# dso_v3b.net
KiCad netlist of a schematic drawn in EAGLE
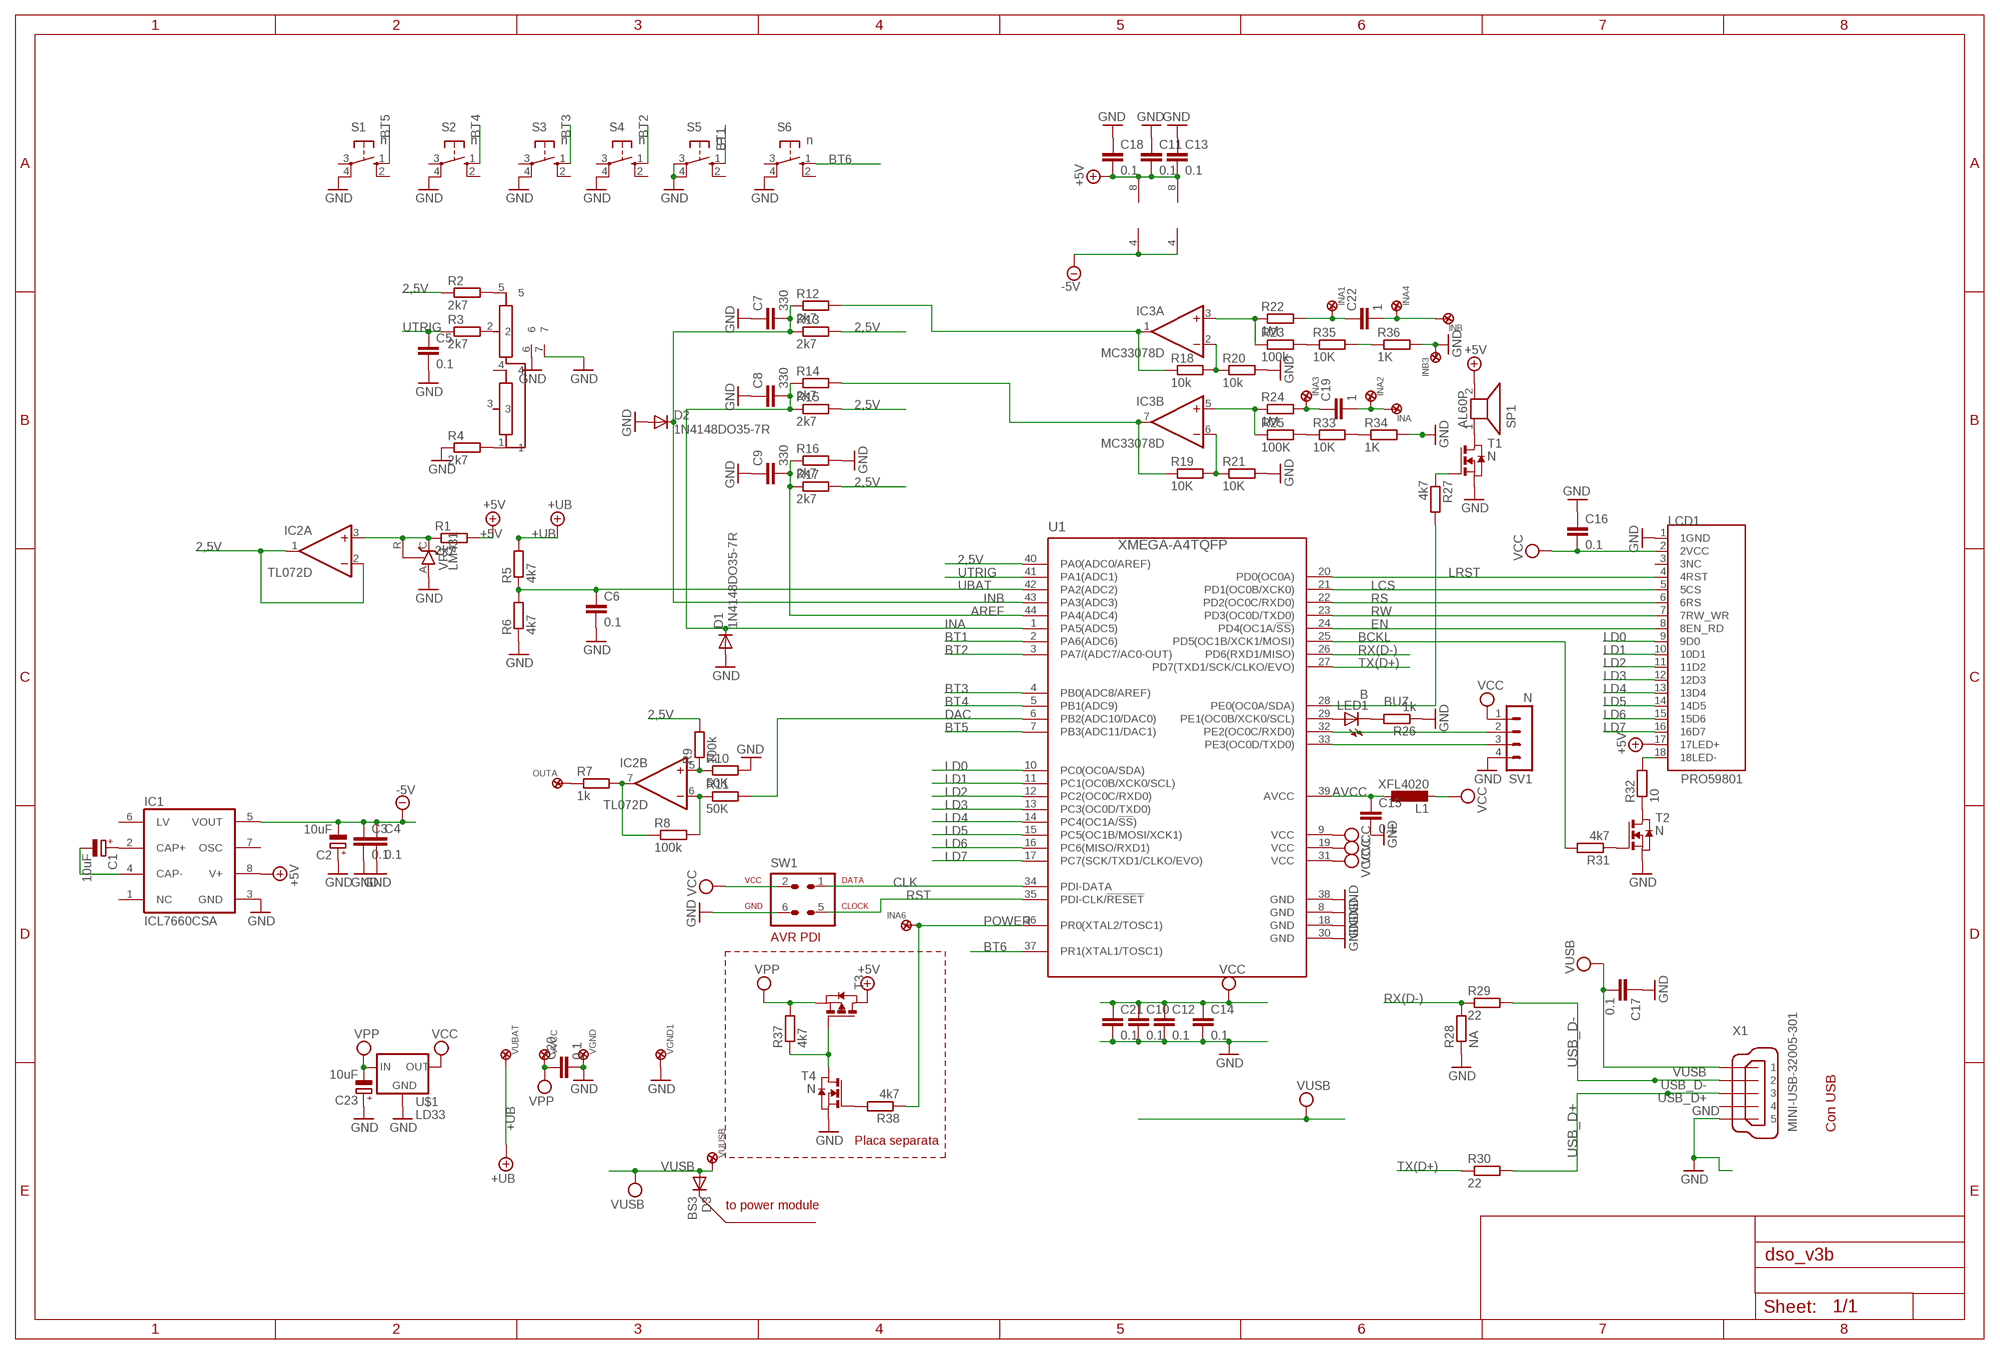
[diagram p0: schematic, sheet 1]

(export (version "E")
  (design (tool "Eeschema 10.0.6"))
  (components
    (comp (ref "C1")
      (value "10uF")
      (footprint "eagle-import:CT3528")
      (libsource (lib "eagle-import") (part "CPOL-EUCT3528"))
    )
    (comp (ref "C2")
      (value "10uF")
      (footprint "eagle-import:CT3528")
      (libsource (lib "eagle-import") (part "CPOL-EUCT3528"))
    )
    (comp (ref "C3")
      (value "0.1")
      (footprint "eagle-import:C0603")
      (libsource (lib "eagle-import") (part "C-EUC0603"))
    )
    (comp (ref "C4")
      (value "0.1")
      (footprint "eagle-import:C0603")
      (libsource (lib "eagle-import") (part "C-EUC0603"))
    )
    (comp (ref "C5")
      (value "0.1")
      (footprint "eagle-import:C0603")
      (libsource (lib "eagle-import") (part "C-EUC0603"))
    )
    (comp (ref "C6")
      (value "0.1")
      (footprint "eagle-import:C0603")
      (libsource (lib "eagle-import") (part "C-EUC0603"))
    )
    (comp (ref "C7")
      (value "330")
      (footprint "eagle-import:C025-024X044")
      (libsource (lib "eagle-import") (part "C-EU025-024X044"))
    )
    (comp (ref "C8")
      (value "330")
      (footprint "eagle-import:C025-024X044")
      (libsource (lib "eagle-import") (part "C-EU025-024X044"))
    )
    (comp (ref "C9")
      (value "330")
      (footprint "eagle-import:C025-024X044")
      (libsource (lib "eagle-import") (part "C-EU025-024X044"))
    )
    (comp (ref "C10")
      (value "0.1")
      (footprint "eagle-import:C0603")
      (libsource (lib "eagle-import") (part "C-EUC0603"))
    )
    (comp (ref "C11")
      (value "0.1")
      (footprint "eagle-import:C0603")
      (libsource (lib "eagle-import") (part "C-EUC0603"))
    )
    (comp (ref "C12")
      (value "0.1")
      (footprint "eagle-import:C0603")
      (libsource (lib "eagle-import") (part "C-EUC0603"))
    )
    (comp (ref "C13")
      (value "0.1")
      (footprint "eagle-import:SMD_SPECIAL")
      (libsource (lib "eagle-import") (part "C-EUSPEC"))
    )
    (comp (ref "C14")
      (value "0.1")
      (footprint "eagle-import:C0603")
      (libsource (lib "eagle-import") (part "C-EUC0603"))
    )
    (comp (ref "C15")
      (value "0.1")
      (footprint "eagle-import:C0603")
      (libsource (lib "eagle-import") (part "C-EUC0603"))
    )
    (comp (ref "C16")
      (value "0.1")
      (footprint "eagle-import:C0603")
      (libsource (lib "eagle-import") (part "C-EUC0603"))
    )
    (comp (ref "C17")
      (value "0.1")
      (footprint "eagle-import:C1206")
      (libsource (lib "eagle-import") (part "rcl_C-EUC1206"))
    )
    (comp (ref "C18")
      (value "0.1")
      (footprint "eagle-import:C0603")
      (libsource (lib "eagle-import") (part "C-EUC0603"))
    )
    (comp (ref "C19")
      (value "1")
      (footprint "eagle-import:C0603")
      (libsource (lib "eagle-import") (part "C-EUC0603"))
    )
    (comp (ref "C20")
      (value "0.1")
      (footprint "eagle-import:C0805")
      (libsource (lib "eagle-import") (part "C-EUC0805"))
    )
    (comp (ref "C21")
      (value "0.1")
      (footprint "eagle-import:C0805")
      (libsource (lib "eagle-import") (part "C-EUC0805"))
    )
    (comp (ref "C22")
      (value "1")
      (footprint "eagle-import:C0603")
      (libsource (lib "eagle-import") (part "C-EUC0603"))
    )
    (comp (ref "C23")
      (value "10uF")
      (footprint "eagle-import:CT3528")
      (libsource (lib "eagle-import") (part "CPOL-EUCT3528"))
    )
    (comp (ref "D1")
      (value "1N4148DO35-7R")
      (footprint "eagle-import:DO35-7R")
      (libsource (lib "eagle-import") (part "1N4148DO35-7R"))
    )
    (comp (ref "D2")
      (value "1N4148DO35-7R")
      (footprint "eagle-import:DO35-7R")
      (libsource (lib "eagle-import") (part "1N4148DO35-7R"))
    )
    (comp (ref "D3")
      (value "BS3")
      (footprint "eagle-import:DO35-7R")
      (libsource (lib "eagle-import") (part "1N4148DO35-7R"))
    )
    (comp (ref "IC1")
      (value "ICL7660CSA")
      (footprint "eagle-import:SO08")
      (fields (field (name "MF") "MAXIM"))
      (libsource (lib "eagle-import") (part "ICL7660CSA"))
    )
    (comp (ref "IC2")
      (value "TL072D")
      (footprint "eagle-import:SO08")
      (libsource (lib "eagle-import") (part "TL072D"))
    )
    (comp (ref "IC3")
      (value "MC33078D")
      (footprint "eagle-import:SO08")
      (libsource (lib "eagle-import") (part "MC33078D"))
    )
    (comp (ref "INA")
      (value "PADR1")
      (footprint "eagle-import:LP1")
      (libsource (lib "eagle-import") (part "PADR1"))
    )
    (comp (ref "INA1")
      (value "PADR")
      (footprint "eagle-import:LP")
      (libsource (lib "eagle-import") (part "PADR"))
    )
    (comp (ref "INA2")
      (value "PADR")
      (footprint "eagle-import:LP")
      (libsource (lib "eagle-import") (part "PADR"))
    )
    (comp (ref "INA3")
      (value "PADR")
      (footprint "eagle-import:LP")
      (libsource (lib "eagle-import") (part "PADR"))
    )
    (comp (ref "INA4")
      (value "PADR")
      (footprint "eagle-import:LP")
      (libsource (lib "eagle-import") (part "PADR"))
    )
    (comp (ref "INA6")
      (value "PADR1")
      (footprint "eagle-import:LP1")
      (libsource (lib "eagle-import") (part "PADR1"))
    )
    (comp (ref "INB")
      (value "PADR1")
      (footprint "eagle-import:LP1")
      (libsource (lib "eagle-import") (part "PADR1"))
    )
    (comp (ref "INB3")
      (value "PADR1")
      (footprint "eagle-import:LP1")
      (libsource (lib "eagle-import") (part "PADR1"))
    )
    (comp (ref "L1")
      (value "XFL4020")
      (footprint "eagle-import:XFL4020")
      (libsource (lib "eagle-import") (part "XFL4020"))
    )
    (comp (ref "LCD1")
      (value "PRO59801")
      (footprint "eagle-import:PRO59801L")
      (libsource (lib "eagle-import") (part "PRO59801L"))
    )
    (comp (ref "LED1")
      (value "B")
      (footprint "eagle-import:LED3MM")
      (libsource (lib "eagle-import") (part "LED3MM"))
    )
    (comp (ref "OUTA")
      (value "PADR1")
      (footprint "eagle-import:LP1")
      (libsource (lib "eagle-import") (part "PADR1"))
    )
    (comp (ref "P1")
      (value "POT5P")
      (footprint "eagle-import:POT5P")
      (libsource (lib "eagle-import") (part "POT5P"))
    )
    (comp (ref "R1")
      (value "2k7")
      (footprint "eagle-import:0204_7")
      (libsource (lib "eagle-import") (part "R-EU_0204/7"))
    )
    (comp (ref "R2")
      (value "2k7")
      (footprint "eagle-import:R0603")
      (libsource (lib "eagle-import") (part "R-EU_R0603"))
    )
    (comp (ref "R3")
      (value "2k7")
      (footprint "eagle-import:R0603")
      (libsource (lib "eagle-import") (part "R-EU_R0603"))
    )
    (comp (ref "R4")
      (value "2k7")
      (footprint "eagle-import:SMD_SPECIAL")
      (libsource (lib "eagle-import") (part "R-EU_SPEC"))
    )
    (comp (ref "R5")
      (value "4k7")
      (footprint "eagle-import:R0603")
      (libsource (lib "eagle-import") (part "R-EU_R0603"))
    )
    (comp (ref "R6")
      (value "4k7")
      (footprint "eagle-import:R0603")
      (libsource (lib "eagle-import") (part "R-EU_R0603"))
    )
    (comp (ref "R7")
      (value "1k")
      (footprint "eagle-import:R0603")
      (libsource (lib "eagle-import") (part "R-EU_R0603"))
    )
    (comp (ref "R8")
      (value "100k")
      (footprint "eagle-import:R0805")
      (libsource (lib "eagle-import") (part "R-EU_R0805"))
    )
    (comp (ref "R9")
      (value "100k")
      (footprint "eagle-import:R0805")
      (libsource (lib "eagle-import") (part "R-EU_R0805"))
    )
    (comp (ref "R10")
      (value "50K")
      (footprint "eagle-import:R0805")
      (libsource (lib "eagle-import") (part "R-EU_R0805"))
    )
    (comp (ref "R11")
      (value "50K")
      (footprint "eagle-import:SMD_SPECIAL")
      (libsource (lib "eagle-import") (part "R-EU_SPEC"))
    )
    (comp (ref "R12")
      (value "2k7")
      (footprint "eagle-import:SMD_SPECIAL")
      (libsource (lib "eagle-import") (part "R-EU_SPEC"))
    )
    (comp (ref "R13")
      (value "2k7")
      (footprint "eagle-import:R0603")
      (libsource (lib "eagle-import") (part "R-EU_R0603"))
    )
    (comp (ref "R14")
      (value "2k7")
      (footprint "eagle-import:SMD_SPECIAL")
      (libsource (lib "eagle-import") (part "R-EU_SPEC"))
    )
    (comp (ref "R15")
      (value "2k7")
      (footprint "eagle-import:R0603")
      (libsource (lib "eagle-import") (part "R-EU_R0603"))
    )
    (comp (ref "R16")
      (value "2k7")
      (footprint "eagle-import:SMD_SPECIAL")
      (libsource (lib "eagle-import") (part "R-EU_SPEC"))
    )
    (comp (ref "R17")
      (value "2k7")
      (footprint "eagle-import:SMD_SPECIAL")
      (libsource (lib "eagle-import") (part "R-EU_SPEC"))
    )
    (comp (ref "R18")
      (value "10k")
      (footprint "eagle-import:R0805")
      (libsource (lib "eagle-import") (part "R-EU_R0805"))
    )
    (comp (ref "R19")
      (value "10K")
      (footprint "eagle-import:R0805")
      (libsource (lib "eagle-import") (part "R-EU_R0805"))
    )
    (comp (ref "R20")
      (value "10k")
      (footprint "eagle-import:R0805")
      (libsource (lib "eagle-import") (part "R-EU_R0805"))
    )
    (comp (ref "R21")
      (value "10K")
      (footprint "eagle-import:R0805")
      (libsource (lib "eagle-import") (part "R-EU_R0805"))
    )
    (comp (ref "R22")
      (value "1M")
      (footprint "eagle-import:R0805")
      (libsource (lib "eagle-import") (part "R-EU_R0805"))
    )
    (comp (ref "R23")
      (value "100k")
      (footprint "eagle-import:R0805")
      (libsource (lib "eagle-import") (part "R-EU_R0805"))
    )
    (comp (ref "R24")
      (value "1M")
      (footprint "eagle-import:R0805")
      (libsource (lib "eagle-import") (part "R-EU_R0805"))
    )
    (comp (ref "R25")
      (value "100K")
      (footprint "eagle-import:R0603")
      (libsource (lib "eagle-import") (part "R-EU_R0603"))
    )
    (comp (ref "R26")
      (value "1k")
      (footprint "eagle-import:R0603")
      (libsource (lib "eagle-import") (part "R-EU_R0603"))
    )
    (comp (ref "R27")
      (value "4k7")
      (footprint "eagle-import:0204_7")
      (libsource (lib "eagle-import") (part "R-EU_0204/7"))
    )
    (comp (ref "R28")
      (value "NA")
      (footprint "eagle-import:R0603")
      (libsource (lib "eagle-import") (part "R-EU_R0603"))
    )
    (comp (ref "R29")
      (value "22")
      (footprint "eagle-import:R0603")
      (libsource (lib "eagle-import") (part "R-EU_R0603"))
    )
    (comp (ref "R30")
      (value "22")
      (footprint "eagle-import:R0603")
      (libsource (lib "eagle-import") (part "R-EU_R0603"))
    )
    (comp (ref "R31")
      (value "4k7")
      (footprint "eagle-import:R0603")
      (libsource (lib "eagle-import") (part "R-EU_R0603"))
    )
    (comp (ref "R32")
      (value "10")
      (footprint "eagle-import:SMD_SPECIAL")
      (libsource (lib "eagle-import") (part "R-EU_SPEC"))
    )
    (comp (ref "R33")
      (value "10K")
      (footprint "eagle-import:R0805")
      (libsource (lib "eagle-import") (part "R-EU_R0805"))
    )
    (comp (ref "R34")
      (value "1K")
      (footprint "eagle-import:R0603")
      (libsource (lib "eagle-import") (part "R-EU_R0603"))
    )
    (comp (ref "R35")
      (value "10K")
      (footprint "eagle-import:R0805")
      (libsource (lib "eagle-import") (part "R-EU_R0805"))
    )
    (comp (ref "R36")
      (value "1K")
      (footprint "eagle-import:R0603")
      (libsource (lib "eagle-import") (part "R-EU_R0603"))
    )
    (comp (ref "R37")
      (value "4k7")
      (footprint "eagle-import:R0603")
      (libsource (lib "eagle-import") (part "R-EU_R0603"))
    )
    (comp (ref "R38")
      (value "4k7")
      (footprint "eagle-import:R0603")
      (libsource (lib "eagle-import") (part "R-EU_R0603"))
    )
    (comp (ref "S1")
      (value "n")
      (footprint "eagle-import:B3F-10XX")
      (fields (field (name "MPN") "B3F-1000"))
      (libsource (lib "eagle-import") (part "10-XX"))
    )
    (comp (ref "S2")
      (value "n")
      (footprint "eagle-import:B3F-10XX")
      (fields (field (name "MPN") "B3F-1000"))
      (libsource (lib "eagle-import") (part "10-XX"))
    )
    (comp (ref "S3")
      (value "n")
      (footprint "eagle-import:B3F-10XX")
      (fields (field (name "MPN") "B3F-1000"))
      (libsource (lib "eagle-import") (part "10-XX"))
    )
    (comp (ref "S4")
      (value "n")
      (footprint "eagle-import:B3F-10XX")
      (fields (field (name "MPN") "B3F-1000"))
      (libsource (lib "eagle-import") (part "10-XX"))
    )
    (comp (ref "S5")
      (value "n")
      (footprint "eagle-import:B3F-10XX")
      (fields (field (name "MPN") "B3F-1000"))
      (libsource (lib "eagle-import") (part "10-XX"))
    )
    (comp (ref "S6")
      (value "n")
      (footprint "eagle-import:B3F-10XX")
      (fields (field (name "MPN") "B3F-1000"))
      (libsource (lib "eagle-import") (part "10-XX"))
    )
    (comp (ref "SP1")
      (value "AL60P")
      (footprint "eagle-import:AL60P")
      (libsource (lib "eagle-import") (part "AL60P"))
    )
    (comp (ref "SV1")
      (value "N")
      (footprint "eagle-import:MA04-1R")
      (libsource (lib "eagle-import") (part "MA04-1R"))
    )
    (comp (ref "SW1")
      (value "AVR-PDIS")
      (footprint "eagle-import:AVR-ISP-6S")
      (libsource (lib "eagle-import") (part "AVR-PDIS"))
    )
    (comp (ref "T1")
      (value "N")
      (footprint "eagle-import:SOT-23")
      (libsource (lib "eagle-import") (part "NMOSSOT23"))
    )
    (comp (ref "T2")
      (value "N")
      (footprint "eagle-import:SOT-23")
      (libsource (lib "eagle-import") (part "NMOSSOT23"))
    )
    (comp (ref "T3")
      (value "PMOSSOT23")
      (footprint "eagle-import:SOT-23")
      (libsource (lib "eagle-import") (part "PMOSSOT23"))
    )
    (comp (ref "T4")
      (value "N")
      (footprint "eagle-import:SOT-23")
      (libsource (lib "eagle-import") (part "NMOSSOT23"))
    )
    (comp (ref "U$1")
      (value "LD33")
      (footprint "eagle-import:SOT223")
      (libsource (lib "eagle-import") (part "LD33"))
    )
    (comp (ref "U1")
      (value "XMEGA-A4TQFP")
      (footprint "eagle-import:TQFP44")
      (libsource (lib "eagle-import") (part "XMEGA-A4TQFP"))
    )
    (comp (ref "VGND")
      (value "PADR1")
      (footprint "eagle-import:LP1")
      (libsource (lib "eagle-import") (part "PADR1"))
    )
    (comp (ref "VGND1")
      (value "PADR1")
      (footprint "eagle-import:LP1")
      (libsource (lib "eagle-import") (part "PADR1"))
    )
    (comp (ref "VR1")
      (value "LM431")
      (footprint "eagle-import:TO92-CLP")
      (libsource (lib "eagle-import") (part "TL431CLP"))
    )
    (comp (ref "VUBAT")
      (value "PADR1")
      (footprint "eagle-import:LP1")
      (libsource (lib "eagle-import") (part "PADR1"))
    )
    (comp (ref "VUUSB")
      (value "PADR1")
      (footprint "eagle-import:LP1")
      (libsource (lib "eagle-import") (part "PADR1"))
    )
    (comp (ref "VVCC")
      (value "PADR1")
      (footprint "eagle-import:LP1")
      (libsource (lib "eagle-import") (part "PADR1"))
    )
    (comp (ref "X1")
      (value "MINI-USB-32005-301")
      (footprint "eagle-import:32005-301")
      (libsource (lib "eagle-import") (part "MINI-USB-32005-301"))
    )
  )
  (nets
    (net (code "1") (name "+5V") (class "Default")
      (node (ref "C11") (pin "2") (pinfunction "2_2") (pintype "passive"))
      (node (ref "C13") (pin "4") (pinfunction "2_4") (pintype "passive"))
      (node (ref "C18") (pin "2") (pinfunction "2_2") (pintype "passive"))
      (node (ref "IC1") (pin "8") (pinfunction "V+_8") (pintype "power_in"))
      (node (ref "IC2") (pin "8") (pinfunction "V+_8") (pintype "power_in"))
      (node (ref "IC3") (pin "8") (pinfunction "V+_8") (pintype "power_in"))
      (node (ref "LCD1") (pin "17") (pinfunction "17LED+_17") (pintype "bidirectional"))
      (node (ref "R1") (pin "2") (pinfunction "2_2") (pintype "passive"))
      (node (ref "SP1") (pin "2") (pinfunction "2_2") (pintype "passive"))
      (node (ref "T3") (pin "1") (pinfunction "D_1") (pintype "passive"))
    )
    (net (code "2") (name "+UB") (class "Default")
      (node (ref "R5") (pin "2") (pinfunction "2_2") (pintype "passive"))
      (node (ref "VUBAT") (pin "P$1") (pinfunction "P$1_P$1") (pintype "bidirectional"))
    )
    (net (code "3") (name "-5V") (class "Default")
      (node (ref "C2") (pin "-") (pinfunction "-_-") (pintype "passive"))
      (node (ref "C3") (pin "1") (pinfunction "1_1") (pintype "passive"))
      (node (ref "C4") (pin "1") (pinfunction "1_1") (pintype "passive"))
      (node (ref "IC1") (pin "5") (pinfunction "VOUT_5") (pintype "output"))
      (node (ref "IC2") (pin "4") (pinfunction "V-_4") (pintype "power_in"))
      (node (ref "IC3") (pin "4") (pinfunction "V-_4") (pintype "power_in"))
    )
    (net (code "4") (name "/2,5V") (class "Default")
      (node (ref "IC2") (pin "1") (pinfunction "OUT_1") (pintype "output"))
      (node (ref "IC2") (pin "2") (pinfunction "-IN_2") (pintype "input"))
      (node (ref "R13") (pin "2") (pinfunction "2_2") (pintype "passive"))
      (node (ref "R15") (pin "2") (pinfunction "2_2") (pintype "passive"))
      (node (ref "R17") (pin "4") (pinfunction "2_4") (pintype "passive"))
      (node (ref "R2") (pin "1") (pinfunction "1_1") (pintype "passive"))
      (node (ref "R9") (pin "2") (pinfunction "2_2") (pintype "passive"))
      (node (ref "U1") (pin "40") (pinfunction "PA0(ADC0/AREF)_40") (pintype "bidirectional"))
    )
    (net (code "5") (name "/AREF") (class "Default")
      (node (ref "C9") (pin "2") (pinfunction "2_2") (pintype "passive"))
      (node (ref "R16") (pin "3") (pinfunction "1_3") (pintype "passive"))
      (node (ref "R17") (pin "3") (pinfunction "1_3") (pintype "passive"))
      (node (ref "U1") (pin "44") (pinfunction "PA4(ADC4)_44") (pintype "bidirectional"))
    )
    (net (code "6") (name "/AVCC") (class "Default")
      (node (ref "C15") (pin "1") (pinfunction "1_1") (pintype "passive"))
      (node (ref "L1") (pin "P$1") (pinfunction "1_P$1") (pintype "passive"))
      (node (ref "U1") (pin "39") (pinfunction "AVCC_39") (pintype "power_in"))
    )
    (net (code "7") (name "/BCKL") (class "Default")
      (node (ref "R31") (pin "2") (pinfunction "2_2") (pintype "passive"))
      (node (ref "U1") (pin "25") (pinfunction "PD5(OC1B/XCK1/MOSI)_25") (pintype "bidirectional"))
    )
    (net (code "8") (name "/BT1") (class "Default")
      (node (ref "S5") (pin "1") (pinfunction "S_1") (pintype "passive"))
      (node (ref "U1") (pin "2") (pinfunction "PA6(ADC6)_2") (pintype "bidirectional"))
    )
    (net (code "9") (name "/BT2") (class "Default")
      (node (ref "S4") (pin "1") (pinfunction "S_1") (pintype "passive"))
      (node (ref "U1") (pin "3") (pinfunction "PA7/(ADC7/AC0-OUT)_3") (pintype "bidirectional"))
    )
    (net (code "10") (name "/BT3") (class "Default")
      (node (ref "S3") (pin "1") (pinfunction "S_1") (pintype "passive"))
      (node (ref "U1") (pin "4") (pinfunction "PB0(ADC8/AREF)_4") (pintype "bidirectional"))
    )
    (net (code "11") (name "/BT4") (class "Default")
      (node (ref "S2") (pin "1") (pinfunction "S_1") (pintype "passive"))
      (node (ref "U1") (pin "5") (pinfunction "PB1(ADC9)_5") (pintype "bidirectional"))
    )
    (net (code "12") (name "/BT5") (class "Default")
      (node (ref "S1") (pin "1") (pinfunction "S_1") (pintype "passive"))
      (node (ref "U1") (pin "7") (pinfunction "PB3(ADC11/DAC1)_7") (pintype "bidirectional"))
    )
    (net (code "13") (name "/BT6") (class "Default")
      (node (ref "S6") (pin "1") (pinfunction "S_1") (pintype "passive"))
      (node (ref "U1") (pin "37") (pinfunction "PR1(XTAL1/TOSC1)_37") (pintype "bidirectional"))
    )
    (net (code "14") (name "/BUZ") (class "Default")
      (node (ref "R27") (pin "2") (pinfunction "2_2") (pintype "passive"))
      (node (ref "U1") (pin "28") (pinfunction "PE0(OC0A/SDA)_28") (pintype "bidirectional"))
    )
    (net (code "15") (name "/CLK") (class "Default")
      (node (ref "SW1") (pin "1") (pinfunction "1_1") (pintype "passive"))
      (node (ref "U1") (pin "34") (pinfunction "PDI-DATA_34") (pintype "bidirectional"))
    )
    (net (code "16") (name "/DAC") (class "Default")
      (node (ref "R11") (pin "4") (pinfunction "2_4") (pintype "passive"))
      (node (ref "U1") (pin "6") (pinfunction "PB2(ADC10/DAC0)_6") (pintype "bidirectional"))
    )
    (net (code "17") (name "/EN") (class "Default")
      (node (ref "LCD1") (pin "8") (pinfunction "8EN_RD_8") (pintype "bidirectional"))
      (node (ref "U1") (pin "24") (pinfunction "PD4(OC1A/~{SS})_24") (pintype "bidirectional"))
    )
    (net (code "18") (name "/INA") (class "Default")
      (node (ref "C8") (pin "2") (pinfunction "2_2") (pintype "passive"))
      (node (ref "D1") (pin "C") (pinfunction "C_C") (pintype "passive"))
      (node (ref "R14") (pin "3") (pinfunction "1_3") (pintype "passive"))
      (node (ref "R15") (pin "1") (pinfunction "1_1") (pintype "passive"))
      (node (ref "U1") (pin "1") (pinfunction "PA5(ADC5)_1") (pintype "bidirectional"))
    )
    (net (code "19") (name "/INB") (class "Default")
      (node (ref "C7") (pin "2") (pinfunction "2_2") (pintype "passive"))
      (node (ref "D2") (pin "C") (pinfunction "C_C") (pintype "passive"))
      (node (ref "R12") (pin "3") (pinfunction "1_3") (pintype "passive"))
      (node (ref "R13") (pin "1") (pinfunction "1_1") (pintype "passive"))
      (node (ref "U1") (pin "43") (pinfunction "PA3(ADC3)_43") (pintype "bidirectional"))
    )
    (net (code "20") (name "/LCS") (class "Default")
      (node (ref "LCD1") (pin "5") (pinfunction "5CS_5") (pintype "bidirectional"))
      (node (ref "U1") (pin "21") (pinfunction "PD1(OC0B/XCK0)_21") (pintype "bidirectional"))
    )
    (net (code "21") (name "/LD0") (class "Default")
      (node (ref "LCD1") (pin "9") (pinfunction "9D0_9") (pintype "bidirectional"))
      (node (ref "U1") (pin "10") (pinfunction "PC0(OC0A/SDA)_10") (pintype "bidirectional"))
    )
    (net (code "22") (name "/LD1") (class "Default")
      (node (ref "LCD1") (pin "10") (pinfunction "10D1_10") (pintype "bidirectional"))
      (node (ref "U1") (pin "11") (pinfunction "PC1(OC0B/XCK0/SCL)_11") (pintype "bidirectional"))
    )
    (net (code "23") (name "/LD2") (class "Default")
      (node (ref "LCD1") (pin "11") (pinfunction "11D2_11") (pintype "bidirectional"))
      (node (ref "U1") (pin "12") (pinfunction "PC2(OC0C/RXD0)_12") (pintype "bidirectional"))
    )
    (net (code "24") (name "/LD3") (class "Default")
      (node (ref "LCD1") (pin "12") (pinfunction "12D3_12") (pintype "bidirectional"))
      (node (ref "U1") (pin "13") (pinfunction "PC3(OC0D/TXD0)_13") (pintype "bidirectional"))
    )
    (net (code "25") (name "/LD4") (class "Default")
      (node (ref "LCD1") (pin "13") (pinfunction "13D4_13") (pintype "bidirectional"))
      (node (ref "U1") (pin "14") (pinfunction "PC4(OC1A/~{SS})_14") (pintype "bidirectional"))
    )
    (net (code "26") (name "/LD5") (class "Default")
      (node (ref "LCD1") (pin "14") (pinfunction "14D5_14") (pintype "bidirectional"))
      (node (ref "U1") (pin "15") (pinfunction "PC5(OC1B/MOSI/XCK1)_15") (pintype "bidirectional"))
    )
    (net (code "27") (name "/LD6") (class "Default")
      (node (ref "LCD1") (pin "15") (pinfunction "15D6_15") (pintype "bidirectional"))
      (node (ref "U1") (pin "16") (pinfunction "PC6(MISO/RXD1)_16") (pintype "bidirectional"))
    )
    (net (code "28") (name "/LD7") (class "Default")
      (node (ref "LCD1") (pin "16") (pinfunction "16D7_16") (pintype "bidirectional"))
      (node (ref "U1") (pin "17") (pinfunction "PC7(SCK/TXD1/CLKO/EVO)_17") (pintype "bidirectional"))
    )
    (net (code "29") (name "/LRST") (class "Default")
      (node (ref "LCD1") (pin "4") (pinfunction "4RST_4") (pintype "bidirectional"))
      (node (ref "U1") (pin "20") (pinfunction "PD0(OC0A)_20") (pintype "bidirectional"))
    )
    (net (code "30") (name "/POWER") (class "Default")
      (node (ref "INA6") (pin "P$1") (pinfunction "P$1_P$1") (pintype "bidirectional"))
      (node (ref "R38") (pin "1") (pinfunction "1_1") (pintype "passive"))
      (node (ref "U1") (pin "36") (pinfunction "PR0(XTAL2/TOSC1)_36") (pintype "bidirectional"))
    )
    (net (code "31") (name "/RS") (class "Default")
      (node (ref "LCD1") (pin "6") (pinfunction "6RS_6") (pintype "bidirectional"))
      (node (ref "U1") (pin "22") (pinfunction "PD2(OC0C/RXD0)_22") (pintype "bidirectional"))
    )
    (net (code "32") (name "/RST") (class "Default")
      (node (ref "SW1") (pin "5") (pinfunction "5_5") (pintype "passive"))
      (node (ref "U1") (pin "35") (pinfunction "PDI-CLK/~{RESET}_35") (pintype "input"))
    )
    (net (code "33") (name "/RW") (class "Default")
      (node (ref "LCD1") (pin "7") (pinfunction "7RW_WR_7") (pintype "bidirectional"))
      (node (ref "U1") (pin "23") (pinfunction "PD3(OC0D/TXD0)_23") (pintype "bidirectional"))
    )
    (net (code "34") (name "/RX(D-)") (class "Default")
      (node (ref "R28") (pin "2") (pinfunction "2_2") (pintype "passive"))
      (node (ref "R29") (pin "1") (pinfunction "1_1") (pintype "passive"))
      (node (ref "U1") (pin "26") (pinfunction "PD6(RXD1/MISO)_26") (pintype "bidirectional"))
    )
    (net (code "35") (name "/TX(D+)") (class "Default")
      (node (ref "R30") (pin "1") (pinfunction "1_1") (pintype "passive"))
      (node (ref "U1") (pin "27") (pinfunction "PD7(TXD1/SCK/CLKO/EVO)_27") (pintype "bidirectional"))
    )
    (net (code "36") (name "/UBAT") (class "Default")
      (node (ref "C6") (pin "1") (pinfunction "1_1") (pintype "passive"))
      (node (ref "R5") (pin "1") (pinfunction "1_1") (pintype "passive"))
      (node (ref "R6") (pin "2") (pinfunction "2_2") (pintype "passive"))
      (node (ref "U1") (pin "42") (pinfunction "PA2(ADC2)_42") (pintype "bidirectional"))
    )
    (net (code "37") (name "/USB_D+") (class "Default")
      (node (ref "R30") (pin "2") (pinfunction "2_2") (pintype "passive"))
      (node (ref "X1") (pin "3") (pinfunction "3_3") (pintype "passive"))
    )
    (net (code "38") (name "/USB_D-") (class "Default")
      (node (ref "R29") (pin "2") (pinfunction "2_2") (pintype "passive"))
      (node (ref "X1") (pin "2") (pinfunction "2_2") (pintype "passive"))
    )
    (net (code "39") (name "/UTRIG") (class "Default")
      (node (ref "C5") (pin "1") (pinfunction "1_1") (pintype "passive"))
      (node (ref "R3") (pin "1") (pinfunction "1_1") (pintype "passive"))
      (node (ref "U1") (pin "41") (pinfunction "PA1(ADC1)_41") (pintype "bidirectional"))
    )
    (net (code "40") (name "GND") (class "Default")
      (node (ref "C10") (pin "2") (pinfunction "2_2") (pintype "passive"))
      (node (ref "C11") (pin "1") (pinfunction "1_1") (pintype "passive"))
      (node (ref "C12") (pin "2") (pinfunction "2_2") (pintype "passive"))
      (node (ref "C13") (pin "3") (pinfunction "1_3") (pintype "passive"))
      (node (ref "C14") (pin "2") (pinfunction "2_2") (pintype "passive"))
      (node (ref "C15") (pin "2") (pinfunction "2_2") (pintype "passive"))
      (node (ref "C16") (pin "1") (pinfunction "1_1") (pintype "passive"))
      (node (ref "C17") (pin "1") (pinfunction "1_1") (pintype "passive"))
      (node (ref "C18") (pin "1") (pinfunction "1_1") (pintype "passive"))
      (node (ref "C2") (pin "+") (pinfunction "+_+") (pintype "passive"))
      (node (ref "C20") (pin "2") (pinfunction "2_2") (pintype "passive"))
      (node (ref "C21") (pin "2") (pinfunction "2_2") (pintype "passive"))
      (node (ref "C23") (pin "+") (pinfunction "+_+") (pintype "passive"))
      (node (ref "C3") (pin "2") (pinfunction "2_2") (pintype "passive"))
      (node (ref "C4") (pin "2") (pinfunction "2_2") (pintype "passive"))
      (node (ref "C5") (pin "2") (pinfunction "2_2") (pintype "passive"))
      (node (ref "C6") (pin "2") (pinfunction "2_2") (pintype "passive"))
      (node (ref "C7") (pin "1") (pinfunction "1_1") (pintype "passive"))
      (node (ref "C8") (pin "1") (pinfunction "1_1") (pintype "passive"))
      (node (ref "C9") (pin "1") (pinfunction "1_1") (pintype "passive"))
      (node (ref "D1") (pin "A") (pinfunction "A_A") (pintype "passive"))
      (node (ref "D2") (pin "A") (pinfunction "A_A") (pintype "passive"))
      (node (ref "IC1") (pin "3") (pinfunction "GND_3") (pintype "power_in"))
      (node (ref "INB3") (pin "P$1") (pinfunction "P$1_P$1") (pintype "bidirectional"))
      (node (ref "LCD1") (pin "1") (pinfunction "1GND_1") (pintype "bidirectional"))
      (node (ref "P1") (pin "6") (pinfunction "6_6") (pintype "bidirectional"))
      (node (ref "P1") (pin "7") (pinfunction "7_7") (pintype "bidirectional"))
      (node (ref "R10") (pin "2") (pinfunction "2_2") (pintype "passive"))
      (node (ref "R16") (pin "4") (pinfunction "2_4") (pintype "passive"))
      (node (ref "R20") (pin "2") (pinfunction "2_2") (pintype "passive"))
      (node (ref "R21") (pin "2") (pinfunction "2_2") (pintype "passive"))
      (node (ref "R26") (pin "1") (pinfunction "1_1") (pintype "passive"))
      (node (ref "R28") (pin "1") (pinfunction "1_1") (pintype "passive"))
      (node (ref "R34") (pin "2") (pinfunction "2_2") (pintype "passive"))
      (node (ref "R36") (pin "2") (pinfunction "2_2") (pintype "passive"))
      (node (ref "R4") (pin "3") (pinfunction "1_3") (pintype "passive"))
      (node (ref "R6") (pin "1") (pinfunction "1_1") (pintype "passive"))
      (node (ref "S1") (pin "4") (pinfunction "P1_4") (pintype "passive"))
      (node (ref "S2") (pin "4") (pinfunction "P1_4") (pintype "passive"))
      (node (ref "S3") (pin "4") (pinfunction "P1_4") (pintype "passive"))
      (node (ref "S4") (pin "4") (pinfunction "P1_4") (pintype "passive"))
      (node (ref "S5") (pin "3") (pinfunction "P_3") (pintype "passive"))
      (node (ref "S5") (pin "4") (pinfunction "P1_4") (pintype "passive"))
      (node (ref "S6") (pin "4") (pinfunction "P1_4") (pintype "passive"))
      (node (ref "SV1") (pin "4") (pinfunction "4_4") (pintype "passive"))
      (node (ref "SW1") (pin "6") (pinfunction "6_6") (pintype "passive"))
      (node (ref "T1") (pin "2") (pinfunction "S_2") (pintype "passive"))
      (node (ref "T2") (pin "2") (pinfunction "S_2") (pintype "passive"))
      (node (ref "T4") (pin "2") (pinfunction "S_2") (pintype "passive"))
      (node (ref "U$1") (pin "1") (pinfunction "GND_1") (pintype "input"))
      (node (ref "U1") (pin "18") (pinfunction "GND_18") (pintype "power_in"))
      (node (ref "U1") (pin "30") (pinfunction "GND_30") (pintype "power_in"))
      (node (ref "U1") (pin "38") (pinfunction "GND_38") (pintype "power_in"))
      (node (ref "U1") (pin "8") (pinfunction "GND_8") (pintype "power_in"))
      (node (ref "VGND") (pin "P$1") (pinfunction "P$1_P$1") (pintype "bidirectional"))
      (node (ref "VGND1") (pin "P$1") (pinfunction "P$1_P$1") (pintype "bidirectional"))
      (node (ref "VR1") (pin "A") (pinfunction "A_A") (pintype "passive"))
      (node (ref "X1") (pin "5") (pinfunction "5_5") (pintype "passive"))
    )
    (net (code "41") (name "Net-(C19-Pad1)") (class "Default")
      (node (ref "C19") (pin "1") (pinfunction "1_1") (pintype "passive"))
      (node (ref "INA3") (pin "P$1") (pinfunction "P$1_P$1") (pintype "bidirectional"))
      (node (ref "R24") (pin "2") (pinfunction "2_2") (pintype "passive"))
    )
    (net (code "42") (name "Net-(C19-Pad2)") (class "Default")
      (node (ref "C19") (pin "2") (pinfunction "2_2") (pintype "passive"))
      (node (ref "INA") (pin "P$1") (pinfunction "P$1_P$1") (pintype "bidirectional"))
      (node (ref "INA2") (pin "P$1") (pinfunction "P$1_P$1") (pintype "bidirectional"))
    )
    (net (code "43") (name "Net-(C22-Pad1)") (class "Default")
      (node (ref "C22") (pin "1") (pinfunction "1_1") (pintype "passive"))
      (node (ref "INA1") (pin "P$1") (pinfunction "P$1_P$1") (pintype "bidirectional"))
      (node (ref "R22") (pin "2") (pinfunction "2_2") (pintype "passive"))
    )
    (net (code "44") (name "Net-(C22-Pad2)") (class "Default")
      (node (ref "C22") (pin "2") (pinfunction "2_2") (pintype "passive"))
      (node (ref "INA4") (pin "P$1") (pinfunction "P$1_P$1") (pintype "bidirectional"))
      (node (ref "INB") (pin "P$1") (pinfunction "P$1_P$1") (pintype "bidirectional"))
    )
    (net (code "45") (name "Net-(IC1-CAP+)") (class "Default")
      (node (ref "C1") (pin "+") (pinfunction "+_+") (pintype "passive"))
      (node (ref "IC1") (pin "2") (pinfunction "CAP+_2") (pintype "passive"))
    )
    (net (code "46") (name "Net-(IC1-CAP-)") (class "Default")
      (node (ref "C1") (pin "-") (pinfunction "-_-") (pintype "passive"))
      (node (ref "IC1") (pin "4") (pinfunction "CAP-_4") (pintype "passive"))
    )
    (net (code "47") (name "Net-(IC2A-+IN)") (class "Default")
      (node (ref "IC2") (pin "3") (pinfunction "+IN_3") (pintype "input"))
      (node (ref "R1") (pin "1") (pinfunction "1_1") (pintype "passive"))
      (node (ref "VR1") (pin "C") (pinfunction "C_C") (pintype "passive"))
      (node (ref "VR1") (pin "R") (pinfunction "R_R") (pintype "passive"))
    )
    (net (code "48") (name "Net-(IC2B-+IN)") (class "Default")
      (node (ref "IC2") (pin "5") (pinfunction "+IN_5") (pintype "input"))
      (node (ref "R10") (pin "1") (pinfunction "1_1") (pintype "passive"))
      (node (ref "R9") (pin "1") (pinfunction "1_1") (pintype "passive"))
    )
    (net (code "49") (name "Net-(IC2B--IN)") (class "Default")
      (node (ref "IC2") (pin "6") (pinfunction "-IN_6") (pintype "input"))
      (node (ref "R11") (pin "3") (pinfunction "1_3") (pintype "passive"))
      (node (ref "R8") (pin "2") (pinfunction "2_2") (pintype "passive"))
    )
    (net (code "50") (name "Net-(IC2B-OUT)") (class "Default")
      (node (ref "IC2") (pin "7") (pinfunction "OUT_7") (pintype "output"))
      (node (ref "R7") (pin "2") (pinfunction "2_2") (pintype "passive"))
      (node (ref "R8") (pin "1") (pinfunction "1_1") (pintype "passive"))
    )
    (net (code "51") (name "Net-(IC3A-+IN)") (class "Default")
      (node (ref "IC3") (pin "3") (pinfunction "+IN_3") (pintype "input"))
      (node (ref "R22") (pin "1") (pinfunction "1_1") (pintype "passive"))
      (node (ref "R23") (pin "1") (pinfunction "1_1") (pintype "passive"))
    )
    (net (code "52") (name "Net-(IC3A--IN)") (class "Default")
      (node (ref "IC3") (pin "2") (pinfunction "-IN_2") (pintype "input"))
      (node (ref "R18") (pin "2") (pinfunction "2_2") (pintype "passive"))
      (node (ref "R20") (pin "1") (pinfunction "1_1") (pintype "passive"))
    )
    (net (code "53") (name "Net-(IC3A-OUT)") (class "Default")
      (node (ref "IC3") (pin "1") (pinfunction "OUT_1") (pintype "output"))
      (node (ref "R12") (pin "4") (pinfunction "2_4") (pintype "passive"))
      (node (ref "R18") (pin "1") (pinfunction "1_1") (pintype "passive"))
    )
    (net (code "54") (name "Net-(IC3B-+IN)") (class "Default")
      (node (ref "IC3") (pin "5") (pinfunction "+IN_5") (pintype "input"))
      (node (ref "R24") (pin "1") (pinfunction "1_1") (pintype "passive"))
      (node (ref "R25") (pin "1") (pinfunction "1_1") (pintype "passive"))
    )
    (net (code "55") (name "Net-(IC3B--IN)") (class "Default")
      (node (ref "IC3") (pin "6") (pinfunction "-IN_6") (pintype "input"))
      (node (ref "R19") (pin "2") (pinfunction "2_2") (pintype "passive"))
      (node (ref "R21") (pin "1") (pinfunction "1_1") (pintype "passive"))
    )
    (net (code "56") (name "Net-(IC3B-OUT)") (class "Default")
      (node (ref "IC3") (pin "7") (pinfunction "OUT_7") (pintype "output"))
      (node (ref "R14") (pin "4") (pinfunction "2_4") (pintype "passive"))
      (node (ref "R19") (pin "1") (pinfunction "1_1") (pintype "passive"))
    )
    (net (code "57") (name "Net-(LCD1-18LED-)") (class "Default")
      (node (ref "LCD1") (pin "18") (pinfunction "18LED-_18") (pintype "bidirectional"))
      (node (ref "R32") (pin "4") (pinfunction "2_4") (pintype "passive"))
    )
    (net (code "58") (name "Net-(LED1-C)") (class "Default")
      (node (ref "LED1") (pin "K") (pinfunction "C_K") (pintype "passive"))
      (node (ref "R26") (pin "2") (pinfunction "2_2") (pintype "passive"))
    )
    (net (code "59") (name "Net-(OUTA-PadP$1)") (class "Default")
      (node (ref "OUTA") (pin "P$1") (pinfunction "P$1_P$1") (pintype "bidirectional"))
      (node (ref "R7") (pin "1") (pinfunction "1_1") (pintype "passive"))
    )
    (net (code "60") (name "Net-(P1-Pad2)") (class "Default")
      (node (ref "P1") (pin "2") (pinfunction "2_2") (pintype "bidirectional"))
      (node (ref "R3") (pin "2") (pinfunction "2_2") (pintype "passive"))
    )
    (net (code "61") (name "Net-(P1-Pad5)") (class "Default")
      (node (ref "P1") (pin "5") (pinfunction "5_5") (pintype "bidirectional"))
      (node (ref "R2") (pin "2") (pinfunction "2_2") (pintype "passive"))
    )
    (net (code "62") (name "Net-(R4-2)") (class "Default")
      (node (ref "P1") (pin "1") (pinfunction "1_1") (pintype "bidirectional"))
      (node (ref "R4") (pin "4") (pinfunction "2_4") (pintype "passive"))
    )
    (net (code "63") (name "Net-(R23-Pad2)") (class "Default")
      (node (ref "R23") (pin "2") (pinfunction "2_2") (pintype "passive"))
      (node (ref "R35") (pin "1") (pinfunction "1_1") (pintype "passive"))
    )
    (net (code "64") (name "Net-(R25-Pad2)") (class "Default")
      (node (ref "R25") (pin "2") (pinfunction "2_2") (pintype "passive"))
      (node (ref "R33") (pin "1") (pinfunction "1_1") (pintype "passive"))
    )
    (net (code "65") (name "Net-(R32-1)") (class "Default")
      (node (ref "R32") (pin "3") (pinfunction "1_3") (pintype "passive"))
      (node (ref "T2") (pin "1") (pinfunction "D_1") (pintype "passive"))
    )
    (net (code "66") (name "Net-(R33-Pad2)") (class "Default")
      (node (ref "R33") (pin "2") (pinfunction "2_2") (pintype "passive"))
      (node (ref "R34") (pin "1") (pinfunction "1_1") (pintype "passive"))
    )
    (net (code "67") (name "Net-(R35-Pad2)") (class "Default")
      (node (ref "R35") (pin "2") (pinfunction "2_2") (pintype "passive"))
      (node (ref "R36") (pin "1") (pinfunction "1_1") (pintype "passive"))
    )
    (net (code "68") (name "Net-(T1-D)") (class "Default")
      (node (ref "SP1") (pin "1") (pinfunction "1_1") (pintype "passive"))
      (node (ref "T1") (pin "1") (pinfunction "D_1") (pintype "passive"))
    )
    (net (code "69") (name "Net-(T1-G)") (class "Default")
      (node (ref "R27") (pin "1") (pinfunction "1_1") (pintype "passive"))
      (node (ref "T1") (pin "3") (pinfunction "G_3") (pintype "passive"))
    )
    (net (code "70") (name "Net-(T2-G)") (class "Default")
      (node (ref "R31") (pin "1") (pinfunction "1_1") (pintype "passive"))
      (node (ref "T2") (pin "3") (pinfunction "G_3") (pintype "passive"))
    )
    (net (code "71") (name "Net-(T3-G)") (class "Default")
      (node (ref "R37") (pin "1") (pinfunction "1_1") (pintype "passive"))
      (node (ref "T3") (pin "3") (pinfunction "G_3") (pintype "passive"))
      (node (ref "T4") (pin "1") (pinfunction "D_1") (pintype "passive"))
    )
    (net (code "72") (name "Net-(T4-G)") (class "Default")
      (node (ref "R38") (pin "2") (pinfunction "2_2") (pintype "passive"))
      (node (ref "T4") (pin "3") (pinfunction "G_3") (pintype "passive"))
    )
    (net (code "73") (name "Net-(U1-PE1(OC0B{slash}XCK0{slash}SCL))") (class "Default")
      (node (ref "LED1") (pin "A") (pinfunction "A_A") (pintype "passive"))
      (node (ref "U1") (pin "29") (pinfunction "PE1(OC0B/XCK0/SCL)_29") (pintype "bidirectional"))
    )
    (net (code "74") (name "Net-(U1-PE2(OC0C{slash}RXD0))") (class "Default")
      (node (ref "SV1") (pin "2") (pinfunction "2_2") (pintype "passive"))
      (node (ref "U1") (pin "32") (pinfunction "PE2(OC0C/RXD0)_32") (pintype "bidirectional"))
    )
    (net (code "75") (name "Net-(U1-PE3(OC0D{slash}TXD0))") (class "Default")
      (node (ref "SV1") (pin "3") (pinfunction "3_3") (pintype "passive"))
      (node (ref "U1") (pin "33") (pinfunction "PE3(OC0D/TXD0)_33") (pintype "bidirectional"))
    )
    (net (code "76") (name "VCC") (class "Default")
      (node (ref "C10") (pin "1") (pinfunction "1_1") (pintype "passive"))
      (node (ref "C12") (pin "1") (pinfunction "1_1") (pintype "passive"))
      (node (ref "C14") (pin "1") (pinfunction "1_1") (pintype "passive"))
      (node (ref "C16") (pin "2") (pinfunction "2_2") (pintype "passive"))
      (node (ref "C21") (pin "1") (pinfunction "1_1") (pintype "passive"))
      (node (ref "L1") (pin "P$2") (pinfunction "2_P$2") (pintype "passive"))
      (node (ref "LCD1") (pin "2") (pinfunction "2VCC_2") (pintype "bidirectional"))
      (node (ref "SV1") (pin "1") (pinfunction "1_1") (pintype "passive"))
      (node (ref "SW1") (pin "2") (pinfunction "2_2") (pintype "passive"))
      (node (ref "U$1") (pin "2") (pinfunction "OUT_2") (pintype "passive"))
      (node (ref "U$1") (pin "4") (pinfunction "OUT_4") (pintype "passive"))
      (node (ref "U1") (pin "19") (pinfunction "VCC_19") (pintype "power_in"))
      (node (ref "U1") (pin "31") (pinfunction "VCC_31") (pintype "power_in"))
      (node (ref "U1") (pin "9") (pinfunction "VCC_9") (pintype "power_in"))
    )
    (net (code "77") (name "VPP") (class "Default")
      (node (ref "C20") (pin "1") (pinfunction "1_1") (pintype "passive"))
      (node (ref "C23") (pin "-") (pinfunction "-_-") (pintype "passive"))
      (node (ref "R37") (pin "2") (pinfunction "2_2") (pintype "passive"))
      (node (ref "T3") (pin "2") (pinfunction "S_2") (pintype "passive"))
      (node (ref "U$1") (pin "3") (pinfunction "IN_3") (pintype "input"))
      (node (ref "VVCC") (pin "P$1") (pinfunction "P$1_P$1") (pintype "bidirectional"))
    )
    (net (code "78") (name "VUSB") (class "Default")
      (node (ref "C17") (pin "2") (pinfunction "2_2") (pintype "passive"))
      (node (ref "D3") (pin "A") (pinfunction "A_A") (pintype "passive"))
      (node (ref "VUUSB") (pin "P$1") (pinfunction "P$1_P$1") (pintype "bidirectional"))
      (node (ref "X1") (pin "1") (pinfunction "1_1") (pintype "passive"))
    )
    (net (code "79") (name "unconnected-(D3-PadC)") (class "Default")
      (node (ref "D3") (pin "C") (pinfunction "C_C") (pintype "passive"))
    )
    (net (code "80") (name "unconnected-(IC1-LV-Pad6)") (class "Default")
      (node (ref "IC1") (pin "6") (pinfunction "LV_6") (pintype "passive"))
    )
    (net (code "81") (name "unconnected-(IC1-NC-Pad1)") (class "Default")
      (node (ref "IC1") (pin "1") (pinfunction "NC_1") (pintype "no_connect"))
    )
    (net (code "82") (name "unconnected-(IC1-OSC-Pad7)") (class "Default")
      (node (ref "IC1") (pin "7") (pinfunction "OSC_7") (pintype "output"))
    )
    (net (code "83") (name "unconnected-(LCD1-3NC-Pad3)") (class "Default")
      (node (ref "LCD1") (pin "3") (pinfunction "3NC_3") (pintype "bidirectional"))
    )
    (net (code "84") (name "unconnected-(P1-Pad3)") (class "Default")
      (node (ref "P1") (pin "3") (pinfunction "3_3") (pintype "bidirectional"))
    )
    (net (code "85") (name "unconnected-(P1-Pad4)") (class "Default")
      (node (ref "P1") (pin "4") (pinfunction "4_4") (pintype "bidirectional"))
    )
    (net (code "86") (name "unconnected-(S1-P-Pad3)") (class "Default")
      (node (ref "S1") (pin "3") (pinfunction "P_3") (pintype "passive"))
    )
    (net (code "87") (name "unconnected-(S1-S1-Pad2)") (class "Default")
      (node (ref "S1") (pin "2") (pinfunction "S1_2") (pintype "passive"))
    )
    (net (code "88") (name "unconnected-(S2-P-Pad3)") (class "Default")
      (node (ref "S2") (pin "3") (pinfunction "P_3") (pintype "passive"))
    )
    (net (code "89") (name "unconnected-(S2-S1-Pad2)") (class "Default")
      (node (ref "S2") (pin "2") (pinfunction "S1_2") (pintype "passive"))
    )
    (net (code "90") (name "unconnected-(S3-P-Pad3)") (class "Default")
      (node (ref "S3") (pin "3") (pinfunction "P_3") (pintype "passive"))
    )
    (net (code "91") (name "unconnected-(S3-S1-Pad2)") (class "Default")
      (node (ref "S3") (pin "2") (pinfunction "S1_2") (pintype "passive"))
    )
    (net (code "92") (name "unconnected-(S4-P-Pad3)") (class "Default")
      (node (ref "S4") (pin "3") (pinfunction "P_3") (pintype "passive"))
    )
    (net (code "93") (name "unconnected-(S4-S1-Pad2)") (class "Default")
      (node (ref "S4") (pin "2") (pinfunction "S1_2") (pintype "passive"))
    )
    (net (code "94") (name "unconnected-(S5-S1-Pad2)") (class "Default")
      (node (ref "S5") (pin "2") (pinfunction "S1_2") (pintype "passive"))
    )
    (net (code "95") (name "unconnected-(S6-P-Pad3)") (class "Default")
      (node (ref "S6") (pin "3") (pinfunction "P_3") (pintype "passive"))
    )
    (net (code "96") (name "unconnected-(S6-S1-Pad2)") (class "Default")
      (node (ref "S6") (pin "2") (pinfunction "S1_2") (pintype "passive"))
    )
    (net (code "97") (name "unconnected-(X1-Pad4)") (class "Default")
      (node (ref "X1") (pin "4") (pinfunction "4_4") (pintype "passive"))
    )
  )
)
